# do_ph.net
KiCad netlist of a schematic drawn in EAGLE
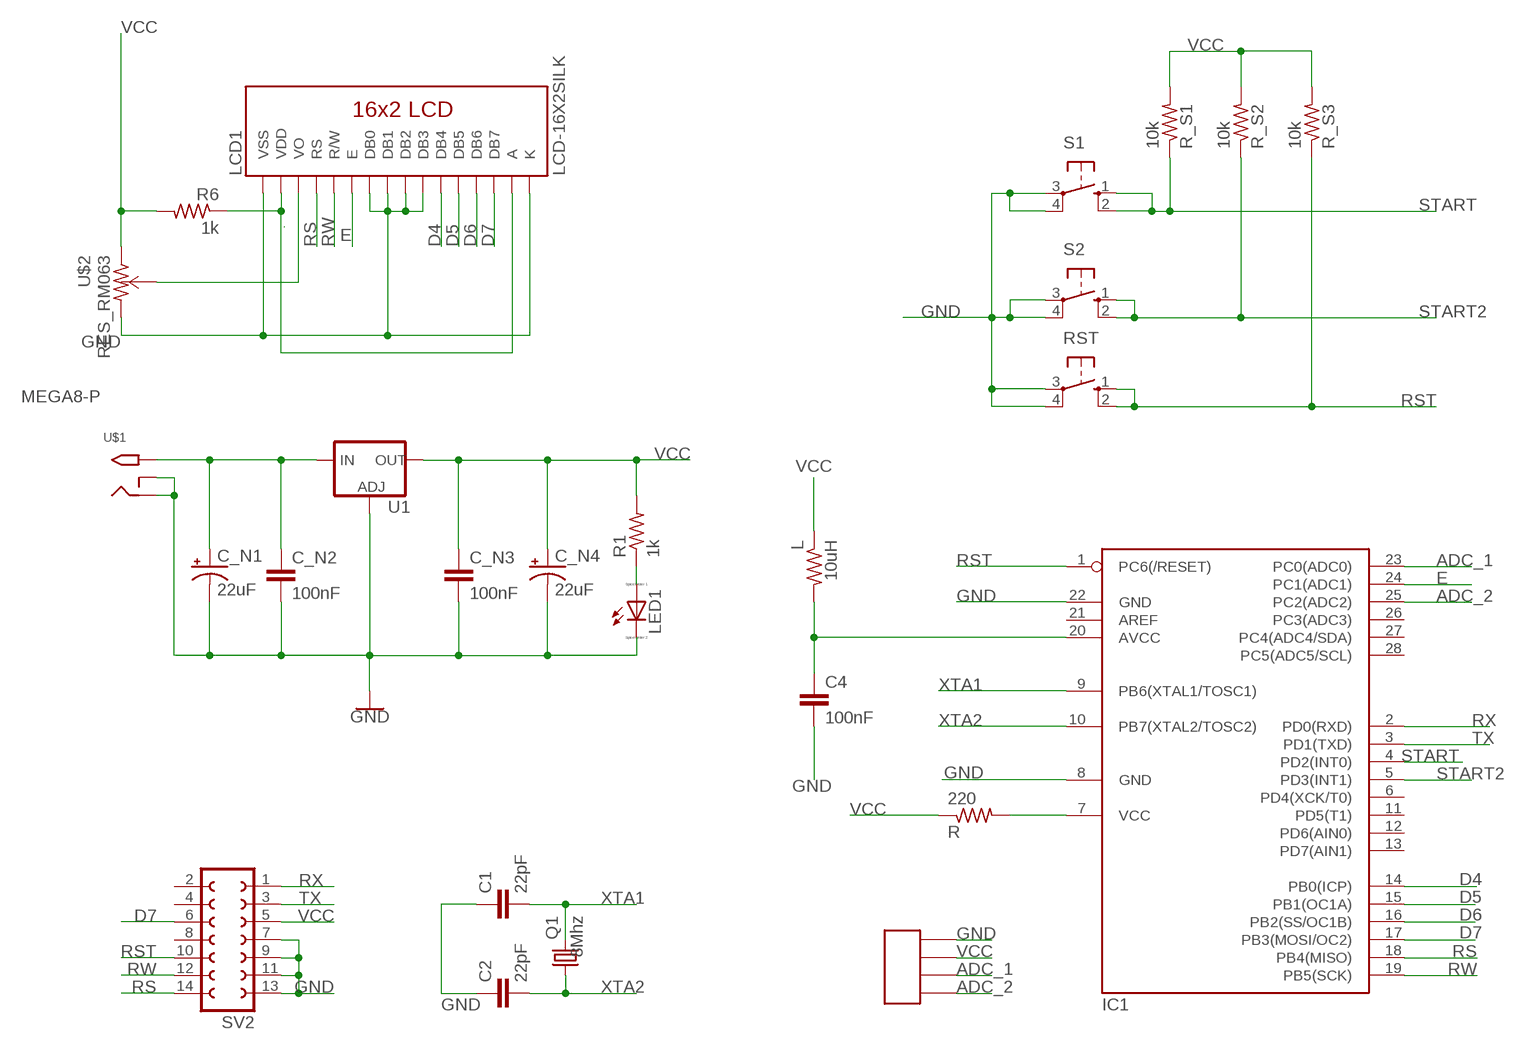
[diagram p0: schematic, sheet 1]

(export (version "E")
  (design (tool "Eeschema 10.0.6"))
  (components
    (comp (ref "C1")
      (value "22pF")
      (footprint "eagle-import:0402-CAP")
      (libsource (lib "eagle-import") (part "2.2UF-CERCAP-07888"))
    )
    (comp (ref "C2")
      (value "22pF")
      (footprint "eagle-import:0402-CAP")
      (libsource (lib "eagle-import") (part "2.2UF-CERCAP-07888"))
    )
    (comp (ref "C4")
      (value "100nF")
      (footprint "eagle-import:0805")
      (libsource (lib "eagle-import") (part "1.0UF-0805-25V-(+80/-20%)"))
    )
    (comp (ref "C_N1")
      (value "22uF")
      (footprint "eagle-import:CT7343")
      (libsource (lib "eagle-import") (part "CPOL-USCT7343"))
    )
    (comp (ref "C_N2")
      (value "100nF")
      (footprint "eagle-import:0805")
      (libsource (lib "eagle-import") (part "1.0UF-0805-25V-(+80/-20%)"))
    )
    (comp (ref "C_N3")
      (value "100nF")
      (footprint "eagle-import:0805")
      (libsource (lib "eagle-import") (part "1.0UF-0805-25V-(+80/-20%)"))
    )
    (comp (ref "C_N4")
      (value "22uF")
      (footprint "eagle-import:CT7343")
      (libsource (lib "eagle-import") (part "CPOL-USCT7343"))
    )
    (comp (ref "IC1")
      (value "MEGA8-P")
      (footprint "eagle-import:DIL28-3")
      (libsource (lib "eagle-import") (part "MEGA8-P"))
    )
    (comp (ref "L")
      (value "10uH")
      (footprint "eagle-import:R0805")
      (libsource (lib "eagle-import") (part "R-US_R0805"))
    )
    (comp (ref "LCD1")
      (value "LCD-16X2SILK")
      (footprint "eagle-import:LCD-16X2")
      (libsource (lib "eagle-import") (part "LCD-16X2SILK"))
    )
    (comp (ref "LED1")
      (value "LED_E")
      (footprint "eagle-import:LED_1206")
      (libsource (lib "eagle-import") (part "LED_E"))
    )
    (comp (ref "Q1")
      (value "8Mhz")
      (footprint "eagle-import:HC49_S")
      (libsource (lib "eagle-import") (part "CRYSTALHC49S"))
    )
    (comp (ref "R")
      (value "220")
      (footprint "eagle-import:R0805")
      (libsource (lib "eagle-import") (part "R-US_R0805"))
    )
    (comp (ref "R1")
      (value "1k")
      (footprint "eagle-import:R0805")
      (libsource (lib "eagle-import") (part "R-US_R0805"))
    )
    (comp (ref "R6")
      (value "1k")
      (footprint "eagle-import:R0805")
      (libsource (lib "eagle-import") (part "R-US_R0805"))
    )
    (comp (ref "RST")
      (value "10-XX")
      (footprint "eagle-import:B3F-10XX")
      (fields (field (name "MPN") "B3F-1000"))
      (libsource (lib "eagle-import") (part "10-XX"))
    )
    (comp (ref "R_S1")
      (value "10k")
      (footprint "eagle-import:R0805")
      (libsource (lib "eagle-import") (part "R-US_R0805"))
    )
    (comp (ref "R_S2")
      (value "10k")
      (footprint "eagle-import:R0805")
      (libsource (lib "eagle-import") (part "R-US_R0805"))
    )
    (comp (ref "R_S3")
      (value "10k")
      (footprint "eagle-import:R0805")
      (libsource (lib "eagle-import") (part "R-US_R0805"))
    )
    (comp (ref "S1")
      (value "10-XX")
      (footprint "eagle-import:B3F-10XX")
      (fields (field (name "MPN") "B3F-1000"))
      (libsource (lib "eagle-import") (part "10-XX"))
    )
    (comp (ref "S2")
      (value "10-XX")
      (footprint "eagle-import:B3F-10XX")
      (fields (field (name "MPN") "B3F-1000"))
      (libsource (lib "eagle-import") (part "10-XX"))
    )
    (comp (ref "SV2")
      (value "FE07-2")
      (footprint "eagle-import:FE07-2")
      (libsource (lib "eagle-import") (part "FE07-2"))
    )
    (comp (ref "U$1")
      (value "2.1MMJACK")
      (footprint "eagle-import:PJ-102A")
      (libsource (lib "eagle-import") (part "2.1MMJACK"))
    )
    (comp (ref "U$2")
      (value "RES_RM063")
      (footprint "eagle-import:RM063")
      (libsource (lib "eagle-import") (part "RES_RM063"))
    )
    (comp (ref "U$5")
      (value "PH_SENSOR_DFROBOT")
      (footprint "eagle-import:PH_DFROBOT")
      (libsource (lib "eagle-import") (part "PH_SENSOR_DFROBOT"))
    )
    (comp (ref "U1")
      (value "V_REG_LM1117SOT223")
      (footprint "eagle-import:SOT223")
      (libsource (lib "eagle-import") (part "V_REG_LM1117SOT223"))
    )
  )
  (nets
    (net (code "1") (name "/ADC_1") (class "Default")
      (node (ref "IC1") (pin "23") (pinfunction "PC0(ADC0)_23") (pintype "bidirectional"))
      (node (ref "U$5") (pin "S_A") (pinfunction "P_A_S_A") (pintype "output"))
    )
    (net (code "2") (name "/ADC_2") (class "Default")
      (node (ref "IC1") (pin "25") (pinfunction "PC2(ADC2)_25") (pintype "bidirectional"))
      (node (ref "U$5") (pin "S_A2") (pinfunction "P_A2_S_A2") (pintype "output"))
    )
    (net (code "3") (name "/D4") (class "Default")
      (node (ref "IC1") (pin "14") (pinfunction "PB0(ICP)_14") (pintype "bidirectional"))
      (node (ref "LCD1") (pin "11") (pinfunction "DB4_11") (pintype "bidirectional"))
    )
    (net (code "4") (name "/D5") (class "Default")
      (node (ref "IC1") (pin "15") (pinfunction "PB1(OC1A)_15") (pintype "bidirectional"))
      (node (ref "LCD1") (pin "12") (pinfunction "DB5_12") (pintype "bidirectional"))
    )
    (net (code "5") (name "/D6") (class "Default")
      (node (ref "IC1") (pin "16") (pinfunction "PB2(SS/OC1B)_16") (pintype "bidirectional"))
      (node (ref "LCD1") (pin "13") (pinfunction "DB6_13") (pintype "bidirectional"))
    )
    (net (code "6") (name "/D7") (class "Default")
      (node (ref "IC1") (pin "17") (pinfunction "PB3(MOSI/OC2)_17") (pintype "bidirectional"))
      (node (ref "LCD1") (pin "14") (pinfunction "DB7_14") (pintype "bidirectional"))
      (node (ref "SV2") (pin "6") (pinfunction "6_6") (pintype "passive"))
    )
    (net (code "7") (name "/E") (class "Default")
      (node (ref "IC1") (pin "24") (pinfunction "PC1(ADC1)_24") (pintype "bidirectional"))
      (node (ref "LCD1") (pin "6") (pinfunction "E_6") (pintype "input"))
    )
    (net (code "8") (name "/RS") (class "Default")
      (node (ref "IC1") (pin "18") (pinfunction "PB4(MISO)_18") (pintype "bidirectional"))
      (node (ref "LCD1") (pin "4") (pinfunction "RS_4") (pintype "input"))
      (node (ref "SV2") (pin "14") (pinfunction "14_14") (pintype "passive"))
    )
    (net (code "9") (name "/RST") (class "Default")
      (node (ref "IC1") (pin "1") (pinfunction "PC6(/RESET)_1") (pintype "bidirectional"))
      (node (ref "RST") (pin "1") (pinfunction "S_1") (pintype "passive"))
      (node (ref "RST") (pin "2") (pinfunction "S1_2") (pintype "passive"))
      (node (ref "R_S3") (pin "1") (pinfunction "1_1") (pintype "passive"))
      (node (ref "SV2") (pin "10") (pinfunction "10_10") (pintype "passive"))
    )
    (net (code "10") (name "/RW") (class "Default")
      (node (ref "IC1") (pin "19") (pinfunction "PB5(SCK)_19") (pintype "bidirectional"))
      (node (ref "LCD1") (pin "5") (pinfunction "R/W_5") (pintype "input"))
      (node (ref "SV2") (pin "12") (pinfunction "12_12") (pintype "passive"))
    )
    (net (code "11") (name "/RX") (class "Default")
      (node (ref "IC1") (pin "2") (pinfunction "PD0(RXD)_2") (pintype "bidirectional"))
      (node (ref "SV2") (pin "1") (pinfunction "1_1") (pintype "passive"))
    )
    (net (code "12") (name "/START") (class "Default")
      (node (ref "IC1") (pin "4") (pinfunction "PD2(INT0)_4") (pintype "bidirectional"))
      (node (ref "R_S1") (pin "1") (pinfunction "1_1") (pintype "passive"))
      (node (ref "S1") (pin "1") (pinfunction "S_1") (pintype "passive"))
      (node (ref "S1") (pin "2") (pinfunction "S1_2") (pintype "passive"))
    )
    (net (code "13") (name "/START2") (class "Default")
      (node (ref "IC1") (pin "5") (pinfunction "PD3(INT1)_5") (pintype "bidirectional"))
      (node (ref "R_S2") (pin "1") (pinfunction "1_1") (pintype "passive"))
      (node (ref "S2") (pin "1") (pinfunction "S_1") (pintype "passive"))
      (node (ref "S2") (pin "2") (pinfunction "S1_2") (pintype "passive"))
    )
    (net (code "14") (name "/TX") (class "Default")
      (node (ref "IC1") (pin "3") (pinfunction "PD1(TXD)_3") (pintype "bidirectional"))
      (node (ref "SV2") (pin "3") (pinfunction "3_3") (pintype "passive"))
    )
    (net (code "15") (name "/VCC") (class "Default")
      (node (ref "C_N3") (pin "1") (pinfunction "1_1") (pintype "passive"))
      (node (ref "C_N4") (pin "+") (pinfunction "+_+") (pintype "passive"))
      (node (ref "L") (pin "1") (pinfunction "1_1") (pintype "passive"))
      (node (ref "R") (pin "1") (pinfunction "1_1") (pintype "passive"))
      (node (ref "R1") (pin "2") (pinfunction "2_2") (pintype "passive"))
      (node (ref "R6") (pin "2") (pinfunction "2_2") (pintype "passive"))
      (node (ref "R_S1") (pin "2") (pinfunction "2_2") (pintype "passive"))
      (node (ref "R_S2") (pin "2") (pinfunction "2_2") (pintype "passive"))
      (node (ref "R_S3") (pin "2") (pinfunction "2_2") (pintype "passive"))
      (node (ref "SV2") (pin "5") (pinfunction "5_5") (pintype "passive"))
      (node (ref "U$2") (pin "P$1") (pinfunction "P$1_P$1") (pintype "bidirectional"))
      (node (ref "U$5") (pin "S_VCC") (pinfunction "P_VCC_S_VCC") (pintype "input"))
      (node (ref "U1") (pin "2") (pinfunction "OUT_2") (pintype "output"))
      (node (ref "U1") (pin "4") (pinfunction "OUT_4") (pintype "output"))
    )
    (net (code "16") (name "/XTA1") (class "Default")
      (node (ref "C1") (pin "2") (pinfunction "2_2") (pintype "passive"))
      (node (ref "IC1") (pin "9") (pinfunction "PB6(XTAL1/TOSC1)_9") (pintype "bidirectional"))
      (node (ref "Q1") (pin "2") (pinfunction "2_2") (pintype "passive"))
    )
    (net (code "17") (name "/XTA2") (class "Default")
      (node (ref "C2") (pin "2") (pinfunction "2_2") (pintype "passive"))
      (node (ref "IC1") (pin "10") (pinfunction "PB7(XTAL2/TOSC2)_10") (pintype "bidirectional"))
      (node (ref "Q1") (pin "1") (pinfunction "1_1") (pintype "passive"))
    )
    (net (code "18") (name "GND") (class "Default")
      (node (ref "C1") (pin "1") (pinfunction "1_1") (pintype "passive"))
      (node (ref "C2") (pin "1") (pinfunction "1_1") (pintype "passive"))
      (node (ref "C4") (pin "2") (pinfunction "2_2") (pintype "passive"))
      (node (ref "C_N1") (pin "-") (pinfunction "-_-") (pintype "passive"))
      (node (ref "C_N2") (pin "2") (pinfunction "2_2") (pintype "passive"))
      (node (ref "C_N3") (pin "2") (pinfunction "2_2") (pintype "passive"))
      (node (ref "C_N4") (pin "-") (pinfunction "-_-") (pintype "passive"))
      (node (ref "IC1") (pin "22") (pinfunction "GND_22") (pintype "power_in"))
      (node (ref "IC1") (pin "8") (pinfunction "GND_8") (pintype "power_in"))
      (node (ref "LCD1") (pin "1") (pinfunction "VSS_1") (pintype "power_in"))
      (node (ref "LCD1") (pin "10") (pinfunction "DB3_10") (pintype "bidirectional"))
      (node (ref "LCD1") (pin "16") (pinfunction "K_16") (pintype "power_in"))
      (node (ref "LCD1") (pin "7") (pinfunction "DB0_7") (pintype "bidirectional"))
      (node (ref "LCD1") (pin "8") (pinfunction "DB1_8") (pintype "bidirectional"))
      (node (ref "LCD1") (pin "9") (pinfunction "DB2_9") (pintype "bidirectional"))
      (node (ref "LED1") (pin "C") (pinfunction "C_C") (pintype "passive"))
      (node (ref "RST") (pin "3") (pinfunction "P_3") (pintype "passive"))
      (node (ref "RST") (pin "4") (pinfunction "P1_4") (pintype "passive"))
      (node (ref "S1") (pin "3") (pinfunction "P_3") (pintype "passive"))
      (node (ref "S1") (pin "4") (pinfunction "P1_4") (pintype "passive"))
      (node (ref "S2") (pin "3") (pinfunction "P_3") (pintype "passive"))
      (node (ref "S2") (pin "4") (pinfunction "P1_4") (pintype "passive"))
      (node (ref "SV2") (pin "11") (pinfunction "11_11") (pintype "passive"))
      (node (ref "SV2") (pin "13") (pinfunction "13_13") (pintype "passive"))
      (node (ref "SV2") (pin "7") (pinfunction "7_7") (pintype "passive"))
      (node (ref "SV2") (pin "9") (pinfunction "9_9") (pintype "passive"))
      (node (ref "U$1") (pin "RING") (pinfunction "RING_RING") (pintype "bidirectional"))
      (node (ref "U$1") (pin "RING_SW") (pinfunction "RING_SW_RING_SW") (pintype "bidirectional"))
      (node (ref "U$2") (pin "P$2") (pinfunction "P$2_P$2") (pintype "bidirectional"))
      (node (ref "U$5") (pin "S_GND") (pinfunction "P_GND_S_GND") (pintype "input"))
      (node (ref "U1") (pin "1") (pinfunction "ADJ_1") (pintype "input"))
    )
    (net (code "19") (name "Net-(IC1-AVCC)") (class "Default")
      (node (ref "C4") (pin "1") (pinfunction "1_1") (pintype "passive"))
      (node (ref "IC1") (pin "20") (pinfunction "AVCC_20") (pintype "power_in"))
      (node (ref "L") (pin "2") (pinfunction "2_2") (pintype "passive"))
    )
    (net (code "20") (name "Net-(IC1-VCC)") (class "Default")
      (node (ref "IC1") (pin "7") (pinfunction "VCC_7") (pintype "power_in"))
      (node (ref "R") (pin "2") (pinfunction "2_2") (pintype "passive"))
    )
    (net (code "21") (name "Net-(LCD1-A)") (class "Default")
      (node (ref "LCD1") (pin "15") (pinfunction "A_15") (pintype "power_in"))
      (node (ref "LCD1") (pin "2") (pinfunction "VDD_2") (pintype "power_in"))
      (node (ref "R6") (pin "1") (pinfunction "1_1") (pintype "passive"))
    )
    (net (code "22") (name "Net-(LCD1-VO)") (class "Default")
      (node (ref "LCD1") (pin "3") (pinfunction "VO_3") (pintype "bidirectional"))
      (node (ref "U$2") (pin "P$3") (pinfunction "P$3_P$3") (pintype "bidirectional"))
    )
    (net (code "23") (name "Net-(LED1-PadA)") (class "Default")
      (node (ref "LED1") (pin "A") (pinfunction "A_A") (pintype "passive"))
      (node (ref "R1") (pin "1") (pinfunction "1_1") (pintype "passive"))
    )
    (net (code "24") (name "Net-(U1-IN)") (class "Default")
      (node (ref "C_N1") (pin "+") (pinfunction "+_+") (pintype "passive"))
      (node (ref "C_N2") (pin "1") (pinfunction "1_1") (pintype "passive"))
      (node (ref "U$1") (pin "TIP") (pinfunction "TIP_TIP") (pintype "bidirectional"))
      (node (ref "U1") (pin "3") (pinfunction "IN_3") (pintype "input"))
    )
    (net (code "25") (name "unconnected-(IC1-AREF-Pad21)") (class "Default")
      (node (ref "IC1") (pin "21") (pinfunction "AREF_21") (pintype "passive"))
    )
    (net (code "26") (name "unconnected-(IC1-PC3(ADC3)-Pad26)") (class "Default")
      (node (ref "IC1") (pin "26") (pinfunction "PC3(ADC3)_26") (pintype "bidirectional"))
    )
    (net (code "27") (name "unconnected-(IC1-PC4(ADC4{slash}SDA)-Pad27)") (class "Default")
      (node (ref "IC1") (pin "27") (pinfunction "PC4(ADC4/SDA)_27") (pintype "bidirectional"))
    )
    (net (code "28") (name "unconnected-(IC1-PC5(ADC5{slash}SCL)-Pad28)") (class "Default")
      (node (ref "IC1") (pin "28") (pinfunction "PC5(ADC5/SCL)_28") (pintype "bidirectional"))
    )
    (net (code "29") (name "unconnected-(IC1-PD4(XCK{slash}T0)-Pad6)") (class "Default")
      (node (ref "IC1") (pin "6") (pinfunction "PD4(XCK/T0)_6") (pintype "bidirectional"))
    )
    (net (code "30") (name "unconnected-(IC1-PD5(T1)-Pad11)") (class "Default")
      (node (ref "IC1") (pin "11") (pinfunction "PD5(T1)_11") (pintype "bidirectional"))
    )
    (net (code "31") (name "unconnected-(IC1-PD6(AIN0)-Pad12)") (class "Default")
      (node (ref "IC1") (pin "12") (pinfunction "PD6(AIN0)_12") (pintype "bidirectional"))
    )
    (net (code "32") (name "unconnected-(IC1-PD7(AIN1)-Pad13)") (class "Default")
      (node (ref "IC1") (pin "13") (pinfunction "PD7(AIN1)_13") (pintype "bidirectional"))
    )
    (net (code "33") (name "unconnected-(SV2-Pad2)") (class "Default")
      (node (ref "SV2") (pin "2") (pinfunction "2_2") (pintype "passive"))
    )
    (net (code "34") (name "unconnected-(SV2-Pad4)") (class "Default")
      (node (ref "SV2") (pin "4") (pinfunction "4_4") (pintype "passive"))
    )
    (net (code "35") (name "unconnected-(SV2-Pad8)") (class "Default")
      (node (ref "SV2") (pin "8") (pinfunction "8_8") (pintype "passive"))
    )
  )
)
